# MezzanineConnectors.net
KiCad netlist of a schematic drawn in Altium Designer
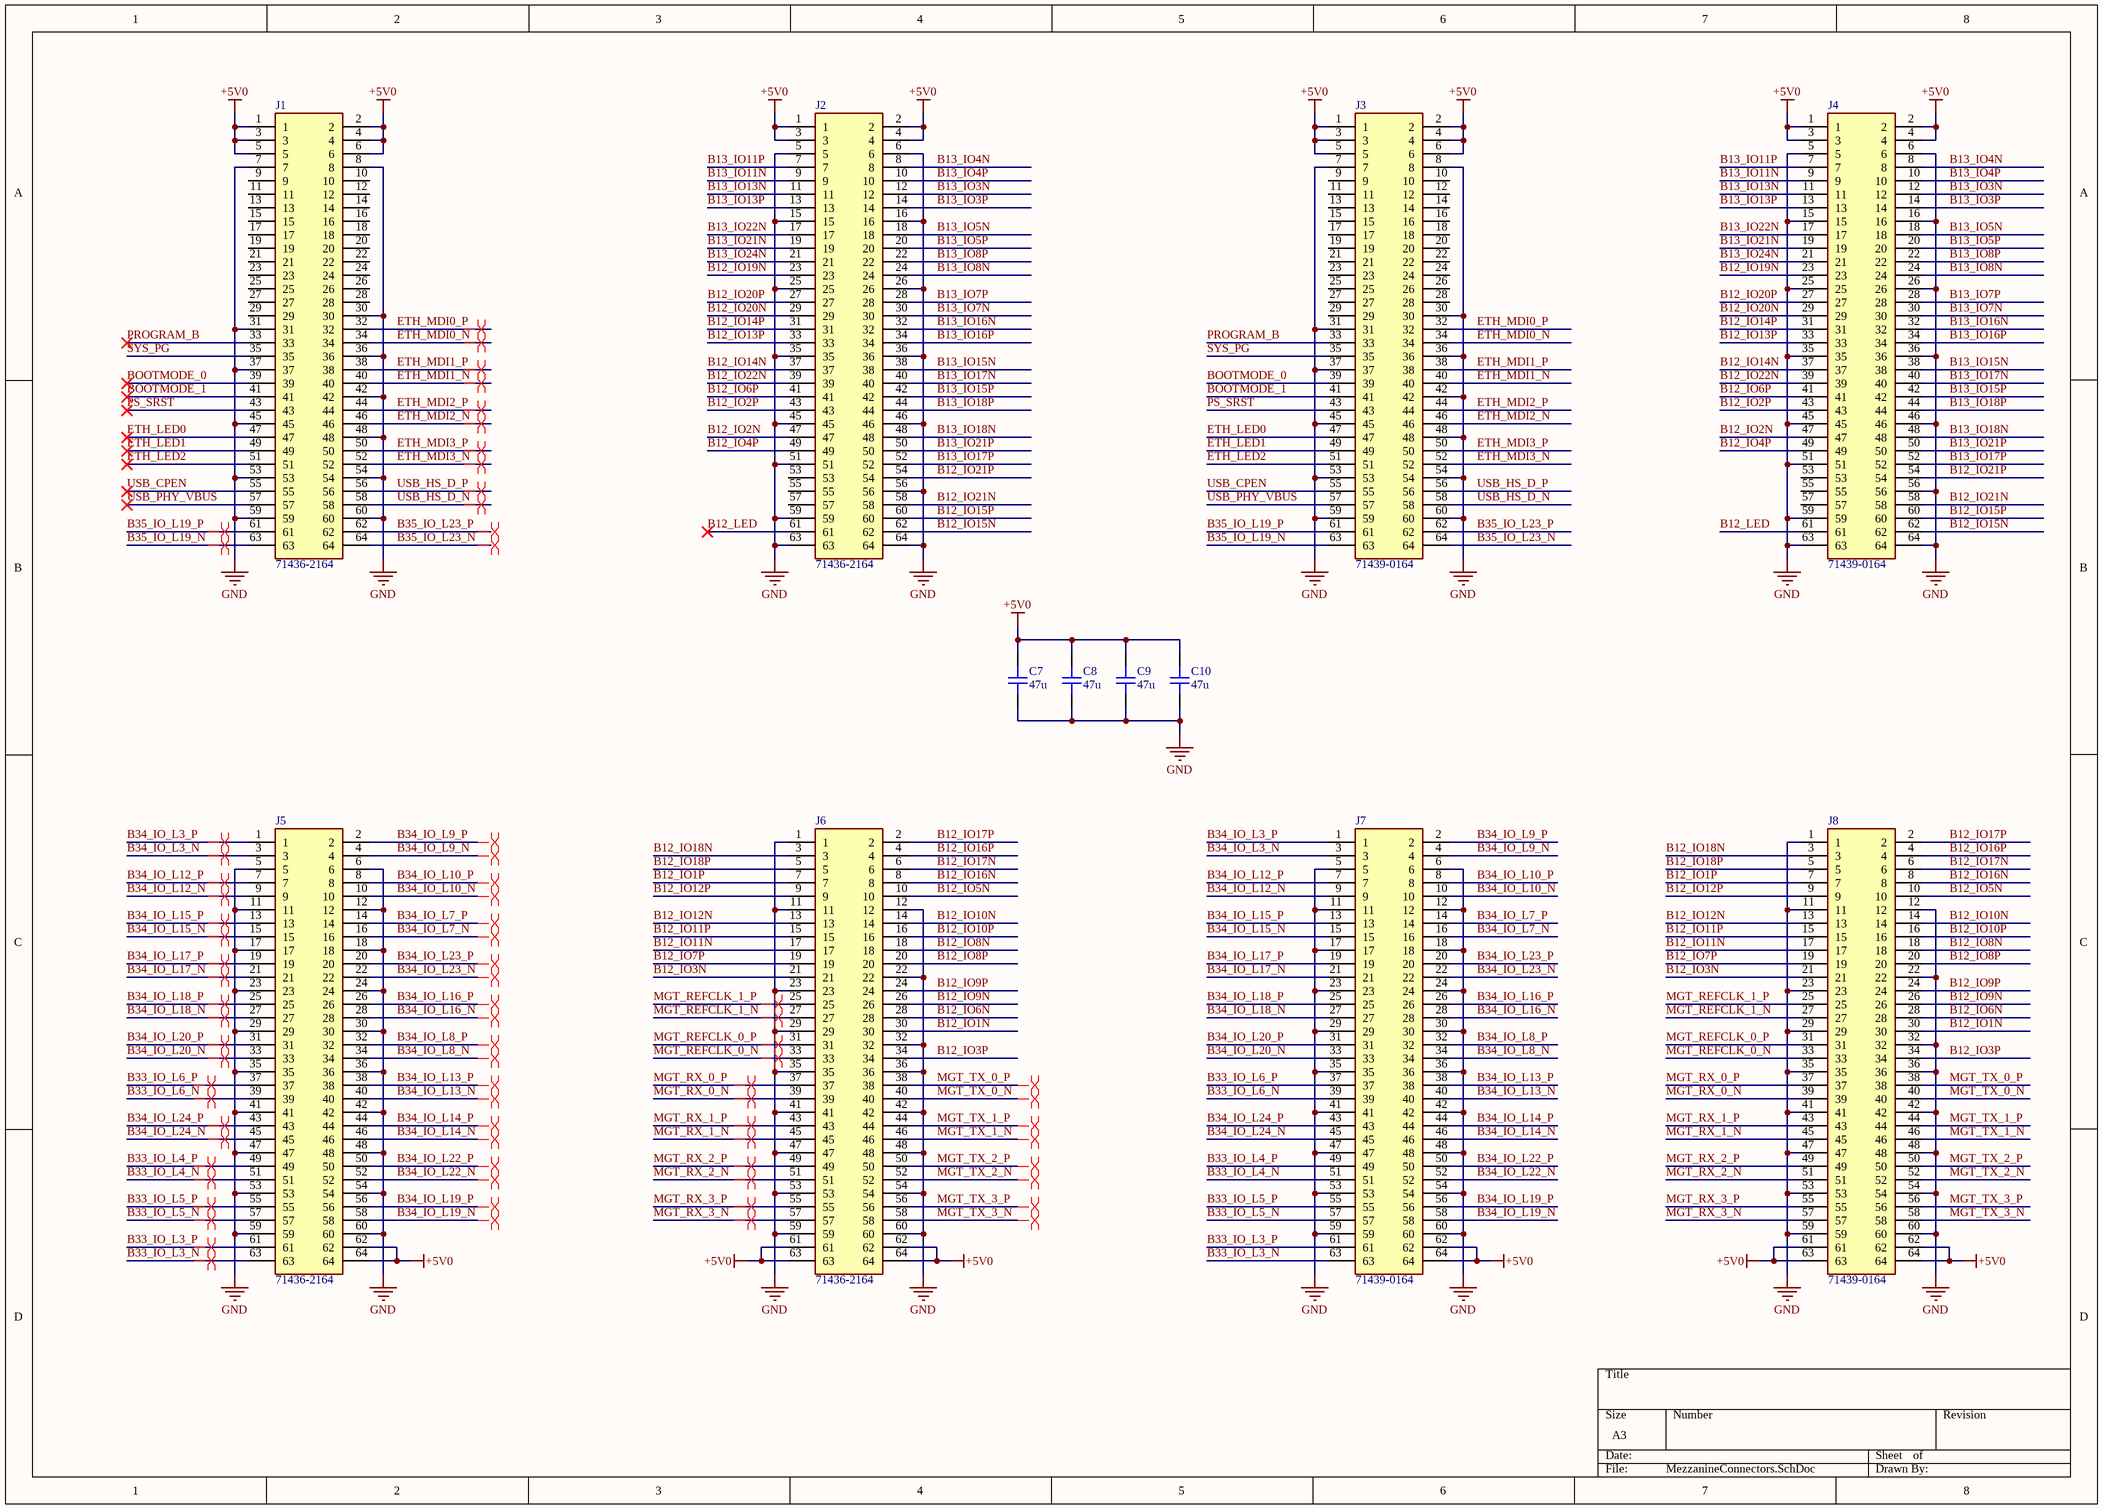
[diagram p0: MezzanineConnectors.SchDoc]

(export (version "E")
  (design (tool "Eeschema 10.0.6"))
  (components
    (comp (ref "C7")
      (value "47u")
      (footprint "CAP_0805")
      (description "Capacitor SMD 0805")
      (libsource (lib "Schematic-Lib-PhilsLab") (part "CAP_0805"))
    )
    (comp (ref "C8")
      (value "47u")
      (footprint "CAP_0805")
      (description "Capacitor SMD 0805")
      (libsource (lib "Schematic-Lib-PhilsLab") (part "CAP_0805"))
    )
    (comp (ref "C9")
      (value "47u")
      (footprint "CAP_0805")
      (description "Capacitor SMD 0805")
      (libsource (lib "Schematic-Lib-PhilsLab") (part "CAP_0805"))
    )
    (comp (ref "C10")
      (value "47u")
      (footprint "CAP_0805")
      (description "Capacitor SMD 0805")
      (libsource (lib "Schematic-Lib-PhilsLab") (part "CAP_0805"))
    )
    (comp (ref "J1")
      (value "71436-2164")
      (footprint "714362164")
      (fields (field (name "MOUSER PART NUMBER") "538-71436-2164"))
      (libsource (lib "XC7Z030SCHLib") (part "71436-2164"))
    )
    (comp (ref "J2")
      (value "71436-2164")
      (footprint "714362164")
      (fields (field (name "MOUSER PART NUMBER") "538-71436-2164"))
      (libsource (lib "XC7Z030SCHLib") (part "71436-2164"))
    )
    (comp (ref "J3")
      (value "71439-0164")
      (footprint "XC7Z030PCBLib:714390164")
      (description "Board to Board & Mezzanine Connectors PMC RECEPTACLE SMT")
      (fields (field (name "MOUSER PART NUMBER") "538-71439-0164"))
      (libsource (lib "XC7Z030SCHLib") (part "71439-0164"))
    )
    (comp (ref "J4")
      (value "71439-0164")
      (footprint "XC7Z030PCBLib:714390164")
      (description "Board to Board & Mezzanine Connectors PMC RECEPTACLE SMT")
      (fields (field (name "MOUSER PART NUMBER") "538-71439-0164"))
      (libsource (lib "XC7Z030SCHLib") (part "71439-0164"))
    )
    (comp (ref "J5")
      (value "71436-2164")
      (footprint "714362164")
      (fields (field (name "MOUSER PART NUMBER") "538-71436-2164"))
      (libsource (lib "XC7Z030SCHLib") (part "71436-2164"))
    )
    (comp (ref "J6")
      (value "71436-2164")
      (footprint "714362164")
      (fields (field (name "MOUSER PART NUMBER") "538-71436-2164"))
      (libsource (lib "XC7Z030SCHLib") (part "71436-2164"))
    )
    (comp (ref "J7")
      (value "71439-0164")
      (footprint "XC7Z030PCBLib:714390164")
      (description "Board to Board & Mezzanine Connectors PMC RECEPTACLE SMT")
      (fields (field (name "MOUSER PART NUMBER") "538-71439-0164"))
      (libsource (lib "XC7Z030SCHLib") (part "71439-0164"))
    )
    (comp (ref "J8")
      (value "71439-0164")
      (footprint "XC7Z030PCBLib:714390164")
      (description "Board to Board & Mezzanine Connectors PMC RECEPTACLE SMT")
      (fields (field (name "MOUSER PART NUMBER") "538-71439-0164"))
      (libsource (lib "XC7Z030SCHLib") (part "71439-0164"))
    )
  )
  (nets
    (net (code "1") (name "+5V0") (class "Default")
      (node (ref "C10") (pin "2") (pinfunction "2_2") (pintype "passive"))
      (node (ref "C7") (pin "2") (pinfunction "2_2") (pintype "passive"))
      (node (ref "C8") (pin "2") (pinfunction "2_2") (pintype "passive"))
      (node (ref "C9") (pin "2") (pinfunction "2_2") (pintype "passive"))
      (node (ref "J1") (pin "1") (pinfunction "1_1") (pintype "passive"))
      (node (ref "J1") (pin "2") (pinfunction "2_2") (pintype "passive"))
      (node (ref "J1") (pin "3") (pinfunction "3_3") (pintype "passive"))
      (node (ref "J1") (pin "4") (pinfunction "4_4") (pintype "passive"))
      (node (ref "J1") (pin "5") (pinfunction "5_5") (pintype "passive"))
      (node (ref "J1") (pin "6") (pinfunction "6_6") (pintype "passive"))
      (node (ref "J2") (pin "1") (pinfunction "1_1") (pintype "passive"))
      (node (ref "J2") (pin "2") (pinfunction "2_2") (pintype "passive"))
      (node (ref "J2") (pin "3") (pinfunction "3_3") (pintype "passive"))
      (node (ref "J2") (pin "4") (pinfunction "4_4") (pintype "passive"))
      (node (ref "J3") (pin "1") (pinfunction "1_1") (pintype "passive"))
      (node (ref "J3") (pin "2") (pinfunction "2_2") (pintype "passive"))
      (node (ref "J3") (pin "3") (pinfunction "3_3") (pintype "passive"))
      (node (ref "J3") (pin "4") (pinfunction "4_4") (pintype "passive"))
      (node (ref "J3") (pin "5") (pinfunction "5_5") (pintype "passive"))
      (node (ref "J3") (pin "6") (pinfunction "6_6") (pintype "passive"))
      (node (ref "J4") (pin "1") (pinfunction "1_1") (pintype "passive"))
      (node (ref "J4") (pin "2") (pinfunction "2_2") (pintype "passive"))
      (node (ref "J4") (pin "3") (pinfunction "3_3") (pintype "passive"))
      (node (ref "J4") (pin "4") (pinfunction "4_4") (pintype "passive"))
      (node (ref "J5") (pin "62") (pinfunction "62_62") (pintype "passive"))
      (node (ref "J5") (pin "64") (pinfunction "64_64") (pintype "passive"))
      (node (ref "J6") (pin "61") (pinfunction "61_61") (pintype "passive"))
      (node (ref "J6") (pin "62") (pinfunction "62_62") (pintype "passive"))
      (node (ref "J6") (pin "63") (pinfunction "63_63") (pintype "passive"))
      (node (ref "J6") (pin "64") (pinfunction "64_64") (pintype "passive"))
      (node (ref "J7") (pin "62") (pinfunction "62_62") (pintype "passive"))
      (node (ref "J7") (pin "64") (pinfunction "64_64") (pintype "passive"))
      (node (ref "J8") (pin "61") (pinfunction "61_61") (pintype "passive"))
      (node (ref "J8") (pin "62") (pinfunction "62_62") (pintype "passive"))
      (node (ref "J8") (pin "63") (pinfunction "63_63") (pintype "passive"))
      (node (ref "J8") (pin "64") (pinfunction "64_64") (pintype "passive"))
    )
    (net (code "2") (name "/B12_IO1N") (class "Default")
      (node (ref "J6") (pin "30") (pinfunction "30_30") (pintype "passive"))
      (node (ref "J8") (pin "30") (pinfunction "30_30") (pintype "passive"))
    )
    (net (code "3") (name "/B12_IO1P") (class "Default")
      (node (ref "J6") (pin "7") (pinfunction "7_7") (pintype "passive"))
      (node (ref "J8") (pin "7") (pinfunction "7_7") (pintype "passive"))
    )
    (net (code "4") (name "/B12_IO2N") (class "Default")
      (node (ref "J2") (pin "47") (pinfunction "47_47") (pintype "passive"))
      (node (ref "J4") (pin "47") (pinfunction "47_47") (pintype "passive"))
    )
    (net (code "5") (name "/B12_IO2P") (class "Default")
      (node (ref "J2") (pin "43") (pinfunction "43_43") (pintype "passive"))
      (node (ref "J4") (pin "43") (pinfunction "43_43") (pintype "passive"))
    )
    (net (code "6") (name "/B12_IO3N") (class "Default")
      (node (ref "J6") (pin "21") (pinfunction "21_21") (pintype "passive"))
      (node (ref "J8") (pin "21") (pinfunction "21_21") (pintype "passive"))
    )
    (net (code "7") (name "/B12_IO3P") (class "Default")
      (node (ref "J6") (pin "34") (pinfunction "34_34") (pintype "passive"))
      (node (ref "J8") (pin "34") (pinfunction "34_34") (pintype "passive"))
    )
    (net (code "8") (name "/B12_IO4P") (class "Default")
      (node (ref "J2") (pin "49") (pinfunction "49_49") (pintype "passive"))
      (node (ref "J4") (pin "49") (pinfunction "49_49") (pintype "passive"))
    )
    (net (code "9") (name "/B12_IO5N") (class "Default")
      (node (ref "J6") (pin "10") (pinfunction "10_10") (pintype "passive"))
      (node (ref "J8") (pin "10") (pinfunction "10_10") (pintype "passive"))
    )
    (net (code "10") (name "/B12_IO6N") (class "Default")
      (node (ref "J6") (pin "28") (pinfunction "28_28") (pintype "passive"))
      (node (ref "J8") (pin "28") (pinfunction "28_28") (pintype "passive"))
    )
    (net (code "11") (name "/B12_IO6P") (class "Default")
      (node (ref "J2") (pin "41") (pinfunction "41_41") (pintype "passive"))
      (node (ref "J4") (pin "41") (pinfunction "41_41") (pintype "passive"))
    )
    (net (code "12") (name "/B12_IO7P") (class "Default")
      (node (ref "J6") (pin "19") (pinfunction "19_19") (pintype "passive"))
      (node (ref "J8") (pin "19") (pinfunction "19_19") (pintype "passive"))
    )
    (net (code "13") (name "/B12_IO8N") (class "Default")
      (node (ref "J6") (pin "18") (pinfunction "18_18") (pintype "passive"))
      (node (ref "J8") (pin "18") (pinfunction "18_18") (pintype "passive"))
    )
    (net (code "14") (name "/B12_IO8P") (class "Default")
      (node (ref "J6") (pin "20") (pinfunction "20_20") (pintype "passive"))
      (node (ref "J8") (pin "20") (pinfunction "20_20") (pintype "passive"))
    )
    (net (code "15") (name "/B12_IO9N") (class "Default")
      (node (ref "J6") (pin "26") (pinfunction "26_26") (pintype "passive"))
      (node (ref "J8") (pin "26") (pinfunction "26_26") (pintype "passive"))
    )
    (net (code "16") (name "/B12_IO9P") (class "Default")
      (node (ref "J6") (pin "24") (pinfunction "24_24") (pintype "passive"))
      (node (ref "J8") (pin "24") (pinfunction "24_24") (pintype "passive"))
    )
    (net (code "17") (name "/B12_IO10N") (class "Default")
      (node (ref "J6") (pin "14") (pinfunction "14_14") (pintype "passive"))
      (node (ref "J8") (pin "14") (pinfunction "14_14") (pintype "passive"))
    )
    (net (code "18") (name "/B12_IO10P") (class "Default")
      (node (ref "J6") (pin "16") (pinfunction "16_16") (pintype "passive"))
      (node (ref "J8") (pin "16") (pinfunction "16_16") (pintype "passive"))
    )
    (net (code "19") (name "/B12_IO11N") (class "Default")
      (node (ref "J6") (pin "17") (pinfunction "17_17") (pintype "passive"))
      (node (ref "J8") (pin "17") (pinfunction "17_17") (pintype "passive"))
    )
    (net (code "20") (name "/B12_IO11P") (class "Default")
      (node (ref "J6") (pin "15") (pinfunction "15_15") (pintype "passive"))
      (node (ref "J8") (pin "15") (pinfunction "15_15") (pintype "passive"))
    )
    (net (code "21") (name "/B12_IO12N") (class "Default")
      (node (ref "J6") (pin "13") (pinfunction "13_13") (pintype "passive"))
      (node (ref "J8") (pin "13") (pinfunction "13_13") (pintype "passive"))
    )
    (net (code "22") (name "/B12_IO12P") (class "Default")
      (node (ref "J6") (pin "9") (pinfunction "9_9") (pintype "passive"))
      (node (ref "J8") (pin "9") (pinfunction "9_9") (pintype "passive"))
    )
    (net (code "23") (name "/B12_IO13P") (class "Default")
      (node (ref "J2") (pin "33") (pinfunction "33_33") (pintype "passive"))
      (node (ref "J4") (pin "33") (pinfunction "33_33") (pintype "passive"))
    )
    (net (code "24") (name "/B12_IO14N") (class "Default")
      (node (ref "J2") (pin "37") (pinfunction "37_37") (pintype "passive"))
      (node (ref "J4") (pin "37") (pinfunction "37_37") (pintype "passive"))
    )
    (net (code "25") (name "/B12_IO14P") (class "Default")
      (node (ref "J2") (pin "31") (pinfunction "31_31") (pintype "passive"))
      (node (ref "J4") (pin "31") (pinfunction "31_31") (pintype "passive"))
    )
    (net (code "26") (name "/B12_IO15N") (class "Default")
      (node (ref "J2") (pin "62") (pinfunction "62_62") (pintype "passive"))
      (node (ref "J4") (pin "62") (pinfunction "62_62") (pintype "passive"))
    )
    (net (code "27") (name "/B12_IO15P") (class "Default")
      (node (ref "J2") (pin "60") (pinfunction "60_60") (pintype "passive"))
      (node (ref "J4") (pin "60") (pinfunction "60_60") (pintype "passive"))
    )
    (net (code "28") (name "/B12_IO16N") (class "Default")
      (node (ref "J6") (pin "8") (pinfunction "8_8") (pintype "passive"))
      (node (ref "J8") (pin "8") (pinfunction "8_8") (pintype "passive"))
    )
    (net (code "29") (name "/B12_IO16P") (class "Default")
      (node (ref "J6") (pin "4") (pinfunction "4_4") (pintype "passive"))
      (node (ref "J8") (pin "4") (pinfunction "4_4") (pintype "passive"))
    )
    (net (code "30") (name "/B12_IO17N") (class "Default")
      (node (ref "J6") (pin "6") (pinfunction "6_6") (pintype "passive"))
      (node (ref "J8") (pin "6") (pinfunction "6_6") (pintype "passive"))
    )
    (net (code "31") (name "/B12_IO17P") (class "Default")
      (node (ref "J6") (pin "2") (pinfunction "2_2") (pintype "passive"))
      (node (ref "J8") (pin "2") (pinfunction "2_2") (pintype "passive"))
    )
    (net (code "32") (name "/B12_IO18N") (class "Default")
      (node (ref "J6") (pin "3") (pinfunction "3_3") (pintype "passive"))
      (node (ref "J8") (pin "3") (pinfunction "3_3") (pintype "passive"))
    )
    (net (code "33") (name "/B12_IO18P") (class "Default")
      (node (ref "J6") (pin "5") (pinfunction "5_5") (pintype "passive"))
      (node (ref "J8") (pin "5") (pinfunction "5_5") (pintype "passive"))
    )
    (net (code "34") (name "/B12_IO19N") (class "Default")
      (node (ref "J2") (pin "23") (pinfunction "23_23") (pintype "passive"))
      (node (ref "J4") (pin "23") (pinfunction "23_23") (pintype "passive"))
    )
    (net (code "35") (name "/B12_IO20N") (class "Default")
      (node (ref "J2") (pin "29") (pinfunction "29_29") (pintype "passive"))
      (node (ref "J4") (pin "29") (pinfunction "29_29") (pintype "passive"))
    )
    (net (code "36") (name "/B12_IO20P") (class "Default")
      (node (ref "J2") (pin "27") (pinfunction "27_27") (pintype "passive"))
      (node (ref "J4") (pin "27") (pinfunction "27_27") (pintype "passive"))
    )
    (net (code "37") (name "/B12_IO21N") (class "Default")
      (node (ref "J2") (pin "58") (pinfunction "58_58") (pintype "passive"))
      (node (ref "J4") (pin "58") (pinfunction "58_58") (pintype "passive"))
    )
    (net (code "38") (name "/B12_IO21P") (class "Default")
      (node (ref "J2") (pin "54") (pinfunction "54_54") (pintype "passive"))
      (node (ref "J4") (pin "54") (pinfunction "54_54") (pintype "passive"))
    )
    (net (code "39") (name "/B12_IO22N") (class "Default")
      (node (ref "J2") (pin "39") (pinfunction "39_39") (pintype "passive"))
      (node (ref "J4") (pin "39") (pinfunction "39_39") (pintype "passive"))
    )
    (net (code "40") (name "/B12_LED") (class "Default")
      (node (ref "J2") (pin "61") (pinfunction "61_61") (pintype "passive"))
      (node (ref "J4") (pin "61") (pinfunction "61_61") (pintype "passive"))
    )
    (net (code "41") (name "/B13_IO3N") (class "Default")
      (node (ref "J2") (pin "12") (pinfunction "12_12") (pintype "passive"))
      (node (ref "J4") (pin "12") (pinfunction "12_12") (pintype "passive"))
    )
    (net (code "42") (name "/B13_IO3P") (class "Default")
      (node (ref "J2") (pin "14") (pinfunction "14_14") (pintype "passive"))
      (node (ref "J4") (pin "14") (pinfunction "14_14") (pintype "passive"))
    )
    (net (code "43") (name "/B13_IO4N") (class "Default")
      (node (ref "J2") (pin "8") (pinfunction "8_8") (pintype "passive"))
      (node (ref "J4") (pin "8") (pinfunction "8_8") (pintype "passive"))
    )
    (net (code "44") (name "/B13_IO4P") (class "Default")
      (node (ref "J2") (pin "10") (pinfunction "10_10") (pintype "passive"))
      (node (ref "J4") (pin "10") (pinfunction "10_10") (pintype "passive"))
    )
    (net (code "45") (name "/B13_IO5N") (class "Default")
      (node (ref "J2") (pin "18") (pinfunction "18_18") (pintype "passive"))
      (node (ref "J4") (pin "18") (pinfunction "18_18") (pintype "passive"))
    )
    (net (code "46") (name "/B13_IO5P") (class "Default")
      (node (ref "J2") (pin "20") (pinfunction "20_20") (pintype "passive"))
      (node (ref "J4") (pin "20") (pinfunction "20_20") (pintype "passive"))
    )
    (net (code "47") (name "/B13_IO7N") (class "Default")
      (node (ref "J2") (pin "30") (pinfunction "30_30") (pintype "passive"))
      (node (ref "J4") (pin "30") (pinfunction "30_30") (pintype "passive"))
    )
    (net (code "48") (name "/B13_IO7P") (class "Default")
      (node (ref "J2") (pin "28") (pinfunction "28_28") (pintype "passive"))
      (node (ref "J4") (pin "28") (pinfunction "28_28") (pintype "passive"))
    )
    (net (code "49") (name "/B13_IO8N") (class "Default")
      (node (ref "J2") (pin "24") (pinfunction "24_24") (pintype "passive"))
      (node (ref "J4") (pin "24") (pinfunction "24_24") (pintype "passive"))
    )
    (net (code "50") (name "/B13_IO8P") (class "Default")
      (node (ref "J2") (pin "22") (pinfunction "22_22") (pintype "passive"))
      (node (ref "J4") (pin "22") (pinfunction "22_22") (pintype "passive"))
    )
    (net (code "51") (name "/B13_IO11N") (class "Default")
      (node (ref "J2") (pin "9") (pinfunction "9_9") (pintype "passive"))
      (node (ref "J4") (pin "9") (pinfunction "9_9") (pintype "passive"))
    )
    (net (code "52") (name "/B13_IO11P") (class "Default")
      (node (ref "J2") (pin "7") (pinfunction "7_7") (pintype "passive"))
      (node (ref "J4") (pin "7") (pinfunction "7_7") (pintype "passive"))
    )
    (net (code "53") (name "/B13_IO13N") (class "Default")
      (node (ref "J2") (pin "11") (pinfunction "11_11") (pintype "passive"))
      (node (ref "J4") (pin "11") (pinfunction "11_11") (pintype "passive"))
    )
    (net (code "54") (name "/B13_IO13P") (class "Default")
      (node (ref "J2") (pin "13") (pinfunction "13_13") (pintype "passive"))
      (node (ref "J4") (pin "13") (pinfunction "13_13") (pintype "passive"))
    )
    (net (code "55") (name "/B13_IO15N") (class "Default")
      (node (ref "J2") (pin "38") (pinfunction "38_38") (pintype "passive"))
      (node (ref "J4") (pin "38") (pinfunction "38_38") (pintype "passive"))
    )
    (net (code "56") (name "/B13_IO15P") (class "Default")
      (node (ref "J2") (pin "42") (pinfunction "42_42") (pintype "passive"))
      (node (ref "J4") (pin "42") (pinfunction "42_42") (pintype "passive"))
    )
    (net (code "57") (name "/B13_IO16N") (class "Default")
      (node (ref "J2") (pin "32") (pinfunction "32_32") (pintype "passive"))
      (node (ref "J4") (pin "32") (pinfunction "32_32") (pintype "passive"))
    )
    (net (code "58") (name "/B13_IO16P") (class "Default")
      (node (ref "J2") (pin "34") (pinfunction "34_34") (pintype "passive"))
      (node (ref "J4") (pin "34") (pinfunction "34_34") (pintype "passive"))
    )
    (net (code "59") (name "/B13_IO17N") (class "Default")
      (node (ref "J2") (pin "40") (pinfunction "40_40") (pintype "passive"))
      (node (ref "J4") (pin "40") (pinfunction "40_40") (pintype "passive"))
    )
    (net (code "60") (name "/B13_IO17P") (class "Default")
      (node (ref "J2") (pin "52") (pinfunction "52_52") (pintype "passive"))
      (node (ref "J4") (pin "52") (pinfunction "52_52") (pintype "passive"))
    )
    (net (code "61") (name "/B13_IO18N") (class "Default")
      (node (ref "J2") (pin "48") (pinfunction "48_48") (pintype "passive"))
      (node (ref "J4") (pin "48") (pinfunction "48_48") (pintype "passive"))
    )
    (net (code "62") (name "/B13_IO18P") (class "Default")
      (node (ref "J2") (pin "44") (pinfunction "44_44") (pintype "passive"))
      (node (ref "J4") (pin "44") (pinfunction "44_44") (pintype "passive"))
    )
    (net (code "63") (name "/B13_IO21N") (class "Default")
      (node (ref "J2") (pin "19") (pinfunction "19_19") (pintype "passive"))
      (node (ref "J4") (pin "19") (pinfunction "19_19") (pintype "passive"))
    )
    (net (code "64") (name "/B13_IO21P") (class "Default")
      (node (ref "J2") (pin "50") (pinfunction "50_50") (pintype "passive"))
      (node (ref "J4") (pin "50") (pinfunction "50_50") (pintype "passive"))
    )
    (net (code "65") (name "/B13_IO22N") (class "Default")
      (node (ref "J2") (pin "17") (pinfunction "17_17") (pintype "passive"))
      (node (ref "J4") (pin "17") (pinfunction "17_17") (pintype "passive"))
    )
    (net (code "66") (name "/B13_IO24N") (class "Default")
      (node (ref "J2") (pin "21") (pinfunction "21_21") (pintype "passive"))
      (node (ref "J4") (pin "21") (pinfunction "21_21") (pintype "passive"))
    )
    (net (code "67") (name "/B33_IO_L3_N") (class "Default")
      (node (ref "J5") (pin "63") (pinfunction "63_63") (pintype "passive"))
      (node (ref "J7") (pin "63") (pinfunction "63_63") (pintype "passive"))
    )
    (net (code "68") (name "/B33_IO_L3_P") (class "Default")
      (node (ref "J5") (pin "61") (pinfunction "61_61") (pintype "passive"))
      (node (ref "J7") (pin "61") (pinfunction "61_61") (pintype "passive"))
    )
    (net (code "69") (name "/B33_IO_L4_N") (class "Default")
      (node (ref "J5") (pin "51") (pinfunction "51_51") (pintype "passive"))
      (node (ref "J7") (pin "51") (pinfunction "51_51") (pintype "passive"))
    )
    (net (code "70") (name "/B33_IO_L4_P") (class "Default")
      (node (ref "J5") (pin "49") (pinfunction "49_49") (pintype "passive"))
      (node (ref "J7") (pin "49") (pinfunction "49_49") (pintype "passive"))
    )
    (net (code "71") (name "/B33_IO_L5_N") (class "Default")
      (node (ref "J5") (pin "57") (pinfunction "57_57") (pintype "passive"))
      (node (ref "J7") (pin "57") (pinfunction "57_57") (pintype "passive"))
    )
    (net (code "72") (name "/B33_IO_L5_P") (class "Default")
      (node (ref "J5") (pin "55") (pinfunction "55_55") (pintype "passive"))
      (node (ref "J7") (pin "55") (pinfunction "55_55") (pintype "passive"))
    )
    (net (code "73") (name "/B33_IO_L6_N") (class "Default")
      (node (ref "J5") (pin "39") (pinfunction "39_39") (pintype "passive"))
      (node (ref "J7") (pin "39") (pinfunction "39_39") (pintype "passive"))
    )
    (net (code "74") (name "/B33_IO_L6_P") (class "Default")
      (node (ref "J5") (pin "37") (pinfunction "37_37") (pintype "passive"))
      (node (ref "J7") (pin "37") (pinfunction "37_37") (pintype "passive"))
    )
    (net (code "75") (name "/B34_IO_L3_N") (class "Default")
      (node (ref "J5") (pin "3") (pinfunction "3_3") (pintype "passive"))
      (node (ref "J7") (pin "3") (pinfunction "3_3") (pintype "passive"))
    )
    (net (code "76") (name "/B34_IO_L3_P") (class "Default")
      (node (ref "J5") (pin "1") (pinfunction "1_1") (pintype "passive"))
      (node (ref "J7") (pin "1") (pinfunction "1_1") (pintype "passive"))
    )
    (net (code "77") (name "/B34_IO_L7_N") (class "Default")
      (node (ref "J5") (pin "16") (pinfunction "16_16") (pintype "passive"))
      (node (ref "J7") (pin "16") (pinfunction "16_16") (pintype "passive"))
    )
    (net (code "78") (name "/B34_IO_L7_P") (class "Default")
      (node (ref "J5") (pin "14") (pinfunction "14_14") (pintype "passive"))
      (node (ref "J7") (pin "14") (pinfunction "14_14") (pintype "passive"))
    )
    (net (code "79") (name "/B34_IO_L8_N") (class "Default")
      (node (ref "J5") (pin "34") (pinfunction "34_34") (pintype "passive"))
      (node (ref "J7") (pin "34") (pinfunction "34_34") (pintype "passive"))
    )
    (net (code "80") (name "/B34_IO_L8_P") (class "Default")
      (node (ref "J5") (pin "32") (pinfunction "32_32") (pintype "passive"))
      (node (ref "J7") (pin "32") (pinfunction "32_32") (pintype "passive"))
    )
    (net (code "81") (name "/B34_IO_L9_N") (class "Default")
      (node (ref "J5") (pin "4") (pinfunction "4_4") (pintype "passive"))
      (node (ref "J7") (pin "4") (pinfunction "4_4") (pintype "passive"))
    )
    (net (code "82") (name "/B34_IO_L9_P") (class "Default")
      (node (ref "J5") (pin "2") (pinfunction "2_2") (pintype "passive"))
      (node (ref "J7") (pin "2") (pinfunction "2_2") (pintype "passive"))
    )
    (net (code "83") (name "/B34_IO_L10_N") (class "Default")
      (node (ref "J5") (pin "10") (pinfunction "10_10") (pintype "passive"))
      (node (ref "J7") (pin "10") (pinfunction "10_10") (pintype "passive"))
    )
    (net (code "84") (name "/B34_IO_L10_P") (class "Default")
      (node (ref "J5") (pin "8") (pinfunction "8_8") (pintype "passive"))
      (node (ref "J7") (pin "8") (pinfunction "8_8") (pintype "passive"))
    )
    (net (code "85") (name "/B34_IO_L12_N") (class "Default")
      (node (ref "J5") (pin "9") (pinfunction "9_9") (pintype "passive"))
      (node (ref "J7") (pin "9") (pinfunction "9_9") (pintype "passive"))
    )
    (net (code "86") (name "/B34_IO_L12_P") (class "Default")
      (node (ref "J5") (pin "7") (pinfunction "7_7") (pintype "passive"))
      (node (ref "J7") (pin "7") (pinfunction "7_7") (pintype "passive"))
    )
    (net (code "87") (name "/B34_IO_L13_N") (class "Default")
      (node (ref "J5") (pin "40") (pinfunction "40_40") (pintype "passive"))
      (node (ref "J7") (pin "40") (pinfunction "40_40") (pintype "passive"))
    )
    (net (code "88") (name "/B34_IO_L13_P") (class "Default")
      (node (ref "J5") (pin "38") (pinfunction "38_38") (pintype "passive"))
      (node (ref "J7") (pin "38") (pinfunction "38_38") (pintype "passive"))
    )
    (net (code "89") (name "/B34_IO_L14_N") (class "Default")
      (node (ref "J5") (pin "46") (pinfunction "46_46") (pintype "passive"))
      (node (ref "J7") (pin "46") (pinfunction "46_46") (pintype "passive"))
    )
    (net (code "90") (name "/B34_IO_L14_P") (class "Default")
      (node (ref "J5") (pin "44") (pinfunction "44_44") (pintype "passive"))
      (node (ref "J7") (pin "44") (pinfunction "44_44") (pintype "passive"))
    )
    (net (code "91") (name "/B34_IO_L15_N") (class "Default")
      (node (ref "J5") (pin "15") (pinfunction "15_15") (pintype "passive"))
      (node (ref "J7") (pin "15") (pinfunction "15_15") (pintype "passive"))
    )
    (net (code "92") (name "/B34_IO_L15_P") (class "Default")
      (node (ref "J5") (pin "13") (pinfunction "13_13") (pintype "passive"))
      (node (ref "J7") (pin "13") (pinfunction "13_13") (pintype "passive"))
    )
    (net (code "93") (name "/B34_IO_L16_N") (class "Default")
      (node (ref "J5") (pin "28") (pinfunction "28_28") (pintype "passive"))
      (node (ref "J7") (pin "28") (pinfunction "28_28") (pintype "passive"))
    )
    (net (code "94") (name "/B34_IO_L16_P") (class "Default")
      (node (ref "J5") (pin "26") (pinfunction "26_26") (pintype "passive"))
      (node (ref "J7") (pin "26") (pinfunction "26_26") (pintype "passive"))
    )
    (net (code "95") (name "/B34_IO_L17_N") (class "Default")
      (node (ref "J5") (pin "21") (pinfunction "21_21") (pintype "passive"))
      (node (ref "J7") (pin "21") (pinfunction "21_21") (pintype "passive"))
    )
    (net (code "96") (name "/B34_IO_L17_P") (class "Default")
      (node (ref "J5") (pin "19") (pinfunction "19_19") (pintype "passive"))
      (node (ref "J7") (pin "19") (pinfunction "19_19") (pintype "passive"))
    )
    (net (code "97") (name "/B34_IO_L18_N") (class "Default")
      (node (ref "J5") (pin "27") (pinfunction "27_27") (pintype "passive"))
      (node (ref "J7") (pin "27") (pinfunction "27_27") (pintype "passive"))
    )
    (net (code "98") (name "/B34_IO_L18_P") (class "Default")
      (node (ref "J5") (pin "25") (pinfunction "25_25") (pintype "passive"))
      (node (ref "J7") (pin "25") (pinfunction "25_25") (pintype "passive"))
    )
    (net (code "99") (name "/B34_IO_L19_N") (class "Default")
      (node (ref "J5") (pin "58") (pinfunction "58_58") (pintype "passive"))
      (node (ref "J7") (pin "58") (pinfunction "58_58") (pintype "passive"))
    )
    (net (code "100") (name "/B34_IO_L19_P") (class "Default")
      (node (ref "J5") (pin "56") (pinfunction "56_56") (pintype "passive"))
      (node (ref "J7") (pin "56") (pinfunction "56_56") (pintype "passive"))
    )
    (net (code "101") (name "/B34_IO_L20_N") (class "Default")
      (node (ref "J5") (pin "33") (pinfunction "33_33") (pintype "passive"))
      (node (ref "J7") (pin "33") (pinfunction "33_33") (pintype "passive"))
    )
    (net (code "102") (name "/B34_IO_L20_P") (class "Default")
      (node (ref "J5") (pin "31") (pinfunction "31_31") (pintype "passive"))
      (node (ref "J7") (pin "31") (pinfunction "31_31") (pintype "passive"))
    )
    (net (code "103") (name "/B34_IO_L22_N") (class "Default")
      (node (ref "J5") (pin "52") (pinfunction "52_52") (pintype "passive"))
      (node (ref "J7") (pin "52") (pinfunction "52_52") (pintype "passive"))
    )
    (net (code "104") (name "/B34_IO_L22_P") (class "Default")
      (node (ref "J5") (pin "50") (pinfunction "50_50") (pintype "passive"))
      (node (ref "J7") (pin "50") (pinfunction "50_50") (pintype "passive"))
    )
    (net (code "105") (name "/B34_IO_L23_N") (class "Default")
      (node (ref "J5") (pin "22") (pinfunction "22_22") (pintype "passive"))
      (node (ref "J7") (pin "22") (pinfunction "22_22") (pintype "passive"))
    )
    (net (code "106") (name "/B34_IO_L23_P") (class "Default")
      (node (ref "J5") (pin "20") (pinfunction "20_20") (pintype "passive"))
      (node (ref "J7") (pin "20") (pinfunction "20_20") (pintype "passive"))
    )
    (net (code "107") (name "/B34_IO_L24_N") (class "Default")
      (node (ref "J5") (pin "45") (pinfunction "45_45") (pintype "passive"))
      (node (ref "J7") (pin "45") (pinfunction "45_45") (pintype "passive"))
    )
    (net (code "108") (name "/B34_IO_L24_P") (class "Default")
      (node (ref "J5") (pin "43") (pinfunction "43_43") (pintype "passive"))
      (node (ref "J7") (pin "43") (pinfunction "43_43") (pintype "passive"))
    )
    (net (code "109") (name "/B35_IO_L19_N") (class "Default")
      (node (ref "J1") (pin "63") (pinfunction "63_63") (pintype "passive"))
      (node (ref "J3") (pin "63") (pinfunction "63_63") (pintype "passive"))
    )
    (net (code "110") (name "/B35_IO_L19_P") (class "Default")
      (node (ref "J1") (pin "61") (pinfunction "61_61") (pintype "passive"))
      (node (ref "J3") (pin "61") (pinfunction "61_61") (pintype "passive"))
    )
    (net (code "111") (name "/B35_IO_L23_N") (class "Default")
      (node (ref "J1") (pin "64") (pinfunction "64_64") (pintype "passive"))
      (node (ref "J3") (pin "64") (pinfunction "64_64") (pintype "passive"))
    )
    (net (code "112") (name "/B35_IO_L23_P") (class "Default")
      (node (ref "J1") (pin "62") (pinfunction "62_62") (pintype "passive"))
      (node (ref "J3") (pin "62") (pinfunction "62_62") (pintype "passive"))
    )
    (net (code "113") (name "/BOOTMODE_0") (class "Default")
      (node (ref "J1") (pin "39") (pinfunction "39_39") (pintype "passive"))
      (node (ref "J3") (pin "39") (pinfunction "39_39") (pintype "passive"))
    )
    (net (code "114") (name "/BOOTMODE_1") (class "Default")
      (node (ref "J1") (pin "41") (pinfunction "41_41") (pintype "passive"))
      (node (ref "J3") (pin "41") (pinfunction "41_41") (pintype "passive"))
    )
    (net (code "115") (name "/ETH_LED0") (class "Default")
      (node (ref "J1") (pin "47") (pinfunction "47_47") (pintype "passive"))
      (node (ref "J3") (pin "47") (pinfunction "47_47") (pintype "passive"))
    )
    (net (code "116") (name "/ETH_LED1") (class "Default")
      (node (ref "J1") (pin "49") (pinfunction "49_49") (pintype "passive"))
      (node (ref "J3") (pin "49") (pinfunction "49_49") (pintype "passive"))
    )
    (net (code "117") (name "/ETH_LED2") (class "Default")
      (node (ref "J1") (pin "51") (pinfunction "51_51") (pintype "passive"))
      (node (ref "J3") (pin "51") (pinfunction "51_51") (pintype "passive"))
    )
    (net (code "118") (name "/ETH_MDI0_N") (class "Default")
      (node (ref "J1") (pin "34") (pinfunction "34_34") (pintype "passive"))
      (node (ref "J3") (pin "34") (pinfunction "34_34") (pintype "passive"))
    )
    (net (code "119") (name "/ETH_MDI0_P") (class "Default")
      (node (ref "J1") (pin "32") (pinfunction "32_32") (pintype "passive"))
      (node (ref "J3") (pin "32") (pinfunction "32_32") (pintype "passive"))
    )
    (net (code "120") (name "/ETH_MDI1_N") (class "Default")
      (node (ref "J1") (pin "40") (pinfunction "40_40") (pintype "passive"))
      (node (ref "J3") (pin "40") (pinfunction "40_40") (pintype "passive"))
    )
    (net (code "121") (name "/ETH_MDI1_P") (class "Default")
      (node (ref "J1") (pin "38") (pinfunction "38_38") (pintype "passive"))
      (node (ref "J3") (pin "38") (pinfunction "38_38") (pintype "passive"))
    )
    (net (code "122") (name "/ETH_MDI2_N") (class "Default")
      (node (ref "J1") (pin "46") (pinfunction "46_46") (pintype "passive"))
      (node (ref "J3") (pin "46") (pinfunction "46_46") (pintype "passive"))
    )
    (net (code "123") (name "/ETH_MDI2_P") (class "Default")
      (node (ref "J1") (pin "44") (pinfunction "44_44") (pintype "passive"))
      (node (ref "J3") (pin "44") (pinfunction "44_44") (pintype "passive"))
    )
    (net (code "124") (name "/ETH_MDI3_N") (class "Default")
      (node (ref "J1") (pin "52") (pinfunction "52_52") (pintype "passive"))
      (node (ref "J3") (pin "52") (pinfunction "52_52") (pintype "passive"))
    )
    (net (code "125") (name "/ETH_MDI3_P") (class "Default")
      (node (ref "J1") (pin "50") (pinfunction "50_50") (pintype "passive"))
      (node (ref "J3") (pin "50") (pinfunction "50_50") (pintype "passive"))
    )
    (net (code "126") (name "/MGT_REFCLK_0_N") (class "Default")
      (node (ref "J6") (pin "33") (pinfunction "33_33") (pintype "passive"))
      (node (ref "J8") (pin "33") (pinfunction "33_33") (pintype "passive"))
    )
    (net (code "127") (name "/MGT_REFCLK_0_P") (class "Default")
      (node (ref "J6") (pin "31") (pinfunction "31_31") (pintype "passive"))
      (node (ref "J8") (pin "31") (pinfunction "31_31") (pintype "passive"))
    )
    (net (code "128") (name "/MGT_REFCLK_1_N") (class "Default")
      (node (ref "J6") (pin "27") (pinfunction "27_27") (pintype "passive"))
      (node (ref "J8") (pin "27") (pinfunction "27_27") (pintype "passive"))
    )
    (net (code "129") (name "/MGT_REFCLK_1_P") (class "Default")
      (node (ref "J6") (pin "25") (pinfunction "25_25") (pintype "passive"))
      (node (ref "J8") (pin "25") (pinfunction "25_25") (pintype "passive"))
    )
    (net (code "130") (name "/MGT_RX_0_N") (class "Default")
      (node (ref "J6") (pin "39") (pinfunction "39_39") (pintype "passive"))
      (node (ref "J8") (pin "39") (pinfunction "39_39") (pintype "passive"))
    )
    (net (code "131") (name "/MGT_RX_0_P") (class "Default")
      (node (ref "J6") (pin "37") (pinfunction "37_37") (pintype "passive"))
      (node (ref "J8") (pin "37") (pinfunction "37_37") (pintype "passive"))
    )
    (net (code "132") (name "/MGT_RX_1_N") (class "Default")
      (node (ref "J6") (pin "45") (pinfunction "45_45") (pintype "passive"))
      (node (ref "J8") (pin "45") (pinfunction "45_45") (pintype "passive"))
    )
    (net (code "133") (name "/MGT_RX_1_P") (class "Default")
      (node (ref "J6") (pin "43") (pinfunction "43_43") (pintype "passive"))
      (node (ref "J8") (pin "43") (pinfunction "43_43") (pintype "passive"))
    )
    (net (code "134") (name "/MGT_RX_2_N") (class "Default")
      (node (ref "J6") (pin "51") (pinfunction "51_51") (pintype "passive"))
      (node (ref "J8") (pin "51") (pinfunction "51_51") (pintype "passive"))
    )
    (net (code "135") (name "/MGT_RX_2_P") (class "Default")
      (node (ref "J6") (pin "49") (pinfunction "49_49") (pintype "passive"))
      (node (ref "J8") (pin "49") (pinfunction "49_49") (pintype "passive"))
    )
    (net (code "136") (name "/MGT_RX_3_N") (class "Default")
      (node (ref "J6") (pin "57") (pinfunction "57_57") (pintype "passive"))
      (node (ref "J8") (pin "57") (pinfunction "57_57") (pintype "passive"))
    )
    (net (code "137") (name "/MGT_RX_3_P") (class "Default")
      (node (ref "J6") (pin "55") (pinfunction "55_55") (pintype "passive"))
      (node (ref "J8") (pin "55") (pinfunction "55_55") (pintype "passive"))
    )
    (net (code "138") (name "/MGT_TX_0_N") (class "Default")
      (node (ref "J6") (pin "40") (pinfunction "40_40") (pintype "passive"))
      (node (ref "J8") (pin "40") (pinfunction "40_40") (pintype "passive"))
    )
    (net (code "139") (name "/MGT_TX_0_P") (class "Default")
      (node (ref "J6") (pin "38") (pinfunction "38_38") (pintype "passive"))
      (node (ref "J8") (pin "38") (pinfunction "38_38") (pintype "passive"))
    )
    (net (code "140") (name "/MGT_TX_1_N") (class "Default")
      (node (ref "J6") (pin "46") (pinfunction "46_46") (pintype "passive"))
      (node (ref "J8") (pin "46") (pinfunction "46_46") (pintype "passive"))
    )
    (net (code "141") (name "/MGT_TX_1_P") (class "Default")
      (node (ref "J6") (pin "44") (pinfunction "44_44") (pintype "passive"))
      (node (ref "J8") (pin "44") (pinfunction "44_44") (pintype "passive"))
    )
    (net (code "142") (name "/MGT_TX_2_N") (class "Default")
      (node (ref "J6") (pin "52") (pinfunction "52_52") (pintype "passive"))
      (node (ref "J8") (pin "52") (pinfunction "52_52") (pintype "passive"))
    )
    (net (code "143") (name "/MGT_TX_2_P") (class "Default")
      (node (ref "J6") (pin "50") (pinfunction "50_50") (pintype "passive"))
      (node (ref "J8") (pin "50") (pinfunction "50_50") (pintype "passive"))
    )
    (net (code "144") (name "/MGT_TX_3_N") (class "Default")
      (node (ref "J6") (pin "58") (pinfunction "58_58") (pintype "passive"))
      (node (ref "J8") (pin "58") (pinfunction "58_58") (pintype "passive"))
    )
    (net (code "145") (name "/MGT_TX_3_P") (class "Default")
      (node (ref "J6") (pin "56") (pinfunction "56_56") (pintype "passive"))
      (node (ref "J8") (pin "56") (pinfunction "56_56") (pintype "passive"))
    )
    (net (code "146") (name "/PROGRAM_B") (class "Default")
      (node (ref "J1") (pin "33") (pinfunction "33_33") (pintype "passive"))
      (node (ref "J3") (pin "33") (pinfunction "33_33") (pintype "passive"))
    )
    (net (code "147") (name "/PS_SRST") (class "Default")
      (node (ref "J1") (pin "43") (pinfunction "43_43") (pintype "passive"))
      (node (ref "J3") (pin "43") (pinfunction "43_43") (pintype "passive"))
    )
    (net (code "148") (name "/SYS_PG") (class "Default")
      (node (ref "J1") (pin "35") (pinfunction "35_35") (pintype "passive"))
      (node (ref "J3") (pin "35") (pinfunction "35_35") (pintype "passive"))
    )
    (net (code "149") (name "/USB_CPEN") (class "Default")
      (node (ref "J1") (pin "55") (pinfunction "55_55") (pintype "passive"))
      (node (ref "J3") (pin "55") (pinfunction "55_55") (pintype "passive"))
    )
    (net (code "150") (name "/USB_HS_D_N") (class "Default")
      (node (ref "J1") (pin "58") (pinfunction "58_58") (pintype "passive"))
      (node (ref "J3") (pin "58") (pinfunction "58_58") (pintype "passive"))
    )
    (net (code "151") (name "/USB_HS_D_P") (class "Default")
      (node (ref "J1") (pin "56") (pinfunction "56_56") (pintype "passive"))
      (node (ref "J3") (pin "56") (pinfunction "56_56") (pintype "passive"))
    )
    (net (code "152") (name "/USB_PHY_VBUS") (class "Default")
      (node (ref "J1") (pin "57") (pinfunction "57_57") (pintype "passive"))
      (node (ref "J3") (pin "57") (pinfunction "57_57") (pintype "passive"))
    )
    (net (code "153") (name "GND") (class "Default")
      (node (ref "C10") (pin "1") (pinfunction "1_1") (pintype "passive"))
      (node (ref "C7") (pin "1") (pinfunction "1_1") (pintype "passive"))
      (node (ref "C8") (pin "1") (pinfunction "1_1") (pintype "passive"))
      (node (ref "C9") (pin "1") (pinfunction "1_1") (pintype "passive"))
      (node (ref "J1") (pin "30") (pinfunction "30_30") (pintype "passive"))
      (node (ref "J1") (pin "31") (pinfunction "31_31") (pintype "passive"))
      (node (ref "J1") (pin "36") (pinfunction "36_36") (pintype "passive"))
      (node (ref "J1") (pin "37") (pinfunction "37_37") (pintype "passive"))
      (node (ref "J1") (pin "42") (pinfunction "42_42") (pintype "passive"))
      (node (ref "J1") (pin "45") (pinfunction "45_45") (pintype "passive"))
      (node (ref "J1") (pin "48") (pinfunction "48_48") (pintype "passive"))
      (node (ref "J1") (pin "53") (pinfunction "53_53") (pintype "passive"))
      (node (ref "J1") (pin "54") (pinfunction "54_54") (pintype "passive"))
      (node (ref "J1") (pin "59") (pinfunction "59_59") (pintype "passive"))
      (node (ref "J1") (pin "60") (pinfunction "60_60") (pintype "passive"))
      (node (ref "J1") (pin "7") (pinfunction "7_7") (pintype "passive"))
      (node (ref "J1") (pin "8") (pinfunction "8_8") (pintype "passive"))
      (node (ref "J2") (pin "15") (pinfunction "15_15") (pintype "passive"))
      (node (ref "J2") (pin "16") (pinfunction "16_16") (pintype "passive"))
      (node (ref "J2") (pin "25") (pinfunction "25_25") (pintype "passive"))
      (node (ref "J2") (pin "26") (pinfunction "26_26") (pintype "passive"))
      (node (ref "J2") (pin "35") (pinfunction "35_35") (pintype "passive"))
      (node (ref "J2") (pin "36") (pinfunction "36_36") (pintype "passive"))
      (node (ref "J2") (pin "45") (pinfunction "45_45") (pintype "passive"))
      (node (ref "J2") (pin "46") (pinfunction "46_46") (pintype "passive"))
      (node (ref "J2") (pin "5") (pinfunction "5_5") (pintype "passive"))
      (node (ref "J2") (pin "51") (pinfunction "51_51") (pintype "passive"))
      (node (ref "J2") (pin "56") (pinfunction "56_56") (pintype "passive"))
      (node (ref "J2") (pin "59") (pinfunction "59_59") (pintype "passive"))
      (node (ref "J2") (pin "6") (pinfunction "6_6") (pintype "passive"))
      (node (ref "J2") (pin "63") (pinfunction "63_63") (pintype "passive"))
      (node (ref "J2") (pin "64") (pinfunction "64_64") (pintype "passive"))
      (node (ref "J3") (pin "30") (pinfunction "30_30") (pintype "passive"))
      (node (ref "J3") (pin "31") (pinfunction "31_31") (pintype "passive"))
      (node (ref "J3") (pin "36") (pinfunction "36_36") (pintype "passive"))
      (node (ref "J3") (pin "37") (pinfunction "37_37") (pintype "passive"))
      (node (ref "J3") (pin "42") (pinfunction "42_42") (pintype "passive"))
      (node (ref "J3") (pin "45") (pinfunction "45_45") (pintype "passive"))
      (node (ref "J3") (pin "48") (pinfunction "48_48") (pintype "passive"))
      (node (ref "J3") (pin "53") (pinfunction "53_53") (pintype "passive"))
      (node (ref "J3") (pin "54") (pinfunction "54_54") (pintype "passive"))
      (node (ref "J3") (pin "59") (pinfunction "59_59") (pintype "passive"))
      (node (ref "J3") (pin "60") (pinfunction "60_60") (pintype "passive"))
      (node (ref "J3") (pin "7") (pinfunction "7_7") (pintype "passive"))
      (node (ref "J3") (pin "8") (pinfunction "8_8") (pintype "passive"))
      (node (ref "J4") (pin "15") (pinfunction "15_15") (pintype "passive"))
      (node (ref "J4") (pin "16") (pinfunction "16_16") (pintype "passive"))
      (node (ref "J4") (pin "25") (pinfunction "25_25") (pintype "passive"))
      (node (ref "J4") (pin "26") (pinfunction "26_26") (pintype "passive"))
      (node (ref "J4") (pin "35") (pinfunction "35_35") (pintype "passive"))
      (node (ref "J4") (pin "36") (pinfunction "36_36") (pintype "passive"))
      (node (ref "J4") (pin "45") (pinfunction "45_45") (pintype "passive"))
      (node (ref "J4") (pin "46") (pinfunction "46_46") (pintype "passive"))
      (node (ref "J4") (pin "5") (pinfunction "5_5") (pintype "passive"))
      (node (ref "J4") (pin "51") (pinfunction "51_51") (pintype "passive"))
      (node (ref "J4") (pin "56") (pinfunction "56_56") (pintype "passive"))
      (node (ref "J4") (pin "59") (pinfunction "59_59") (pintype "passive"))
      (node (ref "J4") (pin "6") (pinfunction "6_6") (pintype "passive"))
      (node (ref "J4") (pin "63") (pinfunction "63_63") (pintype "passive"))
      (node (ref "J4") (pin "64") (pinfunction "64_64") (pintype "passive"))
      (node (ref "J5") (pin "11") (pinfunction "11_11") (pintype "passive"))
      (node (ref "J5") (pin "12") (pinfunction "12_12") (pintype "passive"))
      (node (ref "J5") (pin "17") (pinfunction "17_17") (pintype "passive"))
      (node (ref "J5") (pin "18") (pinfunction "18_18") (pintype "passive"))
      (node (ref "J5") (pin "23") (pinfunction "23_23") (pintype "passive"))
      (node (ref "J5") (pin "24") (pinfunction "24_24") (pintype "passive"))
      (node (ref "J5") (pin "29") (pinfunction "29_29") (pintype "passive"))
      (node (ref "J5") (pin "30") (pinfunction "30_30") (pintype "passive"))
      (node (ref "J5") (pin "35") (pinfunction "35_35") (pintype "passive"))
      (node (ref "J5") (pin "36") (pinfunction "36_36") (pintype "passive"))
      (node (ref "J5") (pin "41") (pinfunction "41_41") (pintype "passive"))
      (node (ref "J5") (pin "42") (pinfunction "42_42") (pintype "passive"))
      (node (ref "J5") (pin "47") (pinfunction "47_47") (pintype "passive"))
      (node (ref "J5") (pin "48") (pinfunction "48_48") (pintype "passive"))
      (node (ref "J5") (pin "5") (pinfunction "5_5") (pintype "passive"))
      (node (ref "J5") (pin "53") (pinfunction "53_53") (pintype "passive"))
      (node (ref "J5") (pin "54") (pinfunction "54_54") (pintype "passive"))
      (node (ref "J5") (pin "59") (pinfunction "59_59") (pintype "passive"))
      (node (ref "J5") (pin "6") (pinfunction "6_6") (pintype "passive"))
      (node (ref "J5") (pin "60") (pinfunction "60_60") (pintype "passive"))
      (node (ref "J6") (pin "1") (pinfunction "1_1") (pintype "passive"))
      (node (ref "J6") (pin "11") (pinfunction "11_11") (pintype "passive"))
      (node (ref "J6") (pin "12") (pinfunction "12_12") (pintype "passive"))
      (node (ref "J6") (pin "22") (pinfunction "22_22") (pintype "passive"))
      (node (ref "J6") (pin "23") (pinfunction "23_23") (pintype "passive"))
      (node (ref "J6") (pin "29") (pinfunction "29_29") (pintype "passive"))
      (node (ref "J6") (pin "32") (pinfunction "32_32") (pintype "passive"))
      (node (ref "J6") (pin "35") (pinfunction "35_35") (pintype "passive"))
      (node (ref "J6") (pin "36") (pinfunction "36_36") (pintype "passive"))
      (node (ref "J6") (pin "41") (pinfunction "41_41") (pintype "passive"))
      (node (ref "J6") (pin "42") (pinfunction "42_42") (pintype "passive"))
      (node (ref "J6") (pin "47") (pinfunction "47_47") (pintype "passive"))
      (node (ref "J6") (pin "48") (pinfunction "48_48") (pintype "passive"))
      (node (ref "J6") (pin "53") (pinfunction "53_53") (pintype "passive"))
      (node (ref "J6") (pin "54") (pinfunction "54_54") (pintype "passive"))
      (node (ref "J6") (pin "59") (pinfunction "59_59") (pintype "passive"))
      (node (ref "J6") (pin "60") (pinfunction "60_60") (pintype "passive"))
      (node (ref "J7") (pin "11") (pinfunction "11_11") (pintype "passive"))
      (node (ref "J7") (pin "12") (pinfunction "12_12") (pintype "passive"))
      (node (ref "J7") (pin "17") (pinfunction "17_17") (pintype "passive"))
      (node (ref "J7") (pin "18") (pinfunction "18_18") (pintype "passive"))
      (node (ref "J7") (pin "23") (pinfunction "23_23") (pintype "passive"))
      (node (ref "J7") (pin "24") (pinfunction "24_24") (pintype "passive"))
      (node (ref "J7") (pin "29") (pinfunction "29_29") (pintype "passive"))
      (node (ref "J7") (pin "30") (pinfunction "30_30") (pintype "passive"))
      (node (ref "J7") (pin "35") (pinfunction "35_35") (pintype "passive"))
      (node (ref "J7") (pin "36") (pinfunction "36_36") (pintype "passive"))
      (node (ref "J7") (pin "41") (pinfunction "41_41") (pintype "passive"))
      (node (ref "J7") (pin "42") (pinfunction "42_42") (pintype "passive"))
      (node (ref "J7") (pin "47") (pinfunction "47_47") (pintype "passive"))
      (node (ref "J7") (pin "48") (pinfunction "48_48") (pintype "passive"))
      (node (ref "J7") (pin "5") (pinfunction "5_5") (pintype "passive"))
      (node (ref "J7") (pin "53") (pinfunction "53_53") (pintype "passive"))
      (node (ref "J7") (pin "54") (pinfunction "54_54") (pintype "passive"))
      (node (ref "J7") (pin "59") (pinfunction "59_59") (pintype "passive"))
      (node (ref "J7") (pin "6") (pinfunction "6_6") (pintype "passive"))
      (node (ref "J7") (pin "60") (pinfunction "60_60") (pintype "passive"))
      (node (ref "J8") (pin "1") (pinfunction "1_1") (pintype "passive"))
      (node (ref "J8") (pin "11") (pinfunction "11_11") (pintype "passive"))
      (node (ref "J8") (pin "12") (pinfunction "12_12") (pintype "passive"))
      (node (ref "J8") (pin "22") (pinfunction "22_22") (pintype "passive"))
      (node (ref "J8") (pin "23") (pinfunction "23_23") (pintype "passive"))
      (node (ref "J8") (pin "29") (pinfunction "29_29") (pintype "passive"))
      (node (ref "J8") (pin "32") (pinfunction "32_32") (pintype "passive"))
      (node (ref "J8") (pin "35") (pinfunction "35_35") (pintype "passive"))
      (node (ref "J8") (pin "36") (pinfunction "36_36") (pintype "passive"))
      (node (ref "J8") (pin "41") (pinfunction "41_41") (pintype "passive"))
      (node (ref "J8") (pin "42") (pinfunction "42_42") (pintype "passive"))
      (node (ref "J8") (pin "47") (pinfunction "47_47") (pintype "passive"))
      (node (ref "J8") (pin "48") (pinfunction "48_48") (pintype "passive"))
      (node (ref "J8") (pin "53") (pinfunction "53_53") (pintype "passive"))
      (node (ref "J8") (pin "54") (pinfunction "54_54") (pintype "passive"))
      (node (ref "J8") (pin "59") (pinfunction "59_59") (pintype "passive"))
      (node (ref "J8") (pin "60") (pinfunction "60_60") (pintype "passive"))
    )
    (net (code "154") (name "unconnected-(J1-Pad9)") (class "Default")
      (node (ref "J1") (pin "9") (pinfunction "9_9") (pintype "passive"))
    )
    (net (code "155") (name "unconnected-(J1-Pad10)") (class "Default")
      (node (ref "J1") (pin "10") (pinfunction "10_10") (pintype "passive"))
    )
    (net (code "156") (name "unconnected-(J1-Pad11)") (class "Default")
      (node (ref "J1") (pin "11") (pinfunction "11_11") (pintype "passive"))
    )
    (net (code "157") (name "unconnected-(J1-Pad12)") (class "Default")
      (node (ref "J1") (pin "12") (pinfunction "12_12") (pintype "passive"))
    )
    (net (code "158") (name "unconnected-(J1-Pad13)") (class "Default")
      (node (ref "J1") (pin "13") (pinfunction "13_13") (pintype "passive"))
    )
    (net (code "159") (name "unconnected-(J1-Pad14)") (class "Default")
      (node (ref "J1") (pin "14") (pinfunction "14_14") (pintype "passive"))
    )
    (net (code "160") (name "unconnected-(J1-Pad15)") (class "Default")
      (node (ref "J1") (pin "15") (pinfunction "15_15") (pintype "passive"))
    )
    (net (code "161") (name "unconnected-(J1-Pad16)") (class "Default")
      (node (ref "J1") (pin "16") (pinfunction "16_16") (pintype "passive"))
    )
    (net (code "162") (name "unconnected-(J1-Pad17)") (class "Default")
      (node (ref "J1") (pin "17") (pinfunction "17_17") (pintype "passive"))
    )
    (net (code "163") (name "unconnected-(J1-Pad18)") (class "Default")
      (node (ref "J1") (pin "18") (pinfunction "18_18") (pintype "passive"))
    )
    (net (code "164") (name "unconnected-(J1-Pad19)") (class "Default")
      (node (ref "J1") (pin "19") (pinfunction "19_19") (pintype "passive"))
    )
    (net (code "165") (name "unconnected-(J1-Pad20)") (class "Default")
      (node (ref "J1") (pin "20") (pinfunction "20_20") (pintype "passive"))
    )
    (net (code "166") (name "unconnected-(J1-Pad21)") (class "Default")
      (node (ref "J1") (pin "21") (pinfunction "21_21") (pintype "passive"))
    )
    (net (code "167") (name "unconnected-(J1-Pad22)") (class "Default")
      (node (ref "J1") (pin "22") (pinfunction "22_22") (pintype "passive"))
    )
    (net (code "168") (name "unconnected-(J1-Pad23)") (class "Default")
      (node (ref "J1") (pin "23") (pinfunction "23_23") (pintype "passive"))
    )
    (net (code "169") (name "unconnected-(J1-Pad24)") (class "Default")
      (node (ref "J1") (pin "24") (pinfunction "24_24") (pintype "passive"))
    )
    (net (code "170") (name "unconnected-(J1-Pad25)") (class "Default")
      (node (ref "J1") (pin "25") (pinfunction "25_25") (pintype "passive"))
    )
    (net (code "171") (name "unconnected-(J1-Pad26)") (class "Default")
      (node (ref "J1") (pin "26") (pinfunction "26_26") (pintype "passive"))
    )
    (net (code "172") (name "unconnected-(J1-Pad27)") (class "Default")
      (node (ref "J1") (pin "27") (pinfunction "27_27") (pintype "passive"))
    )
    (net (code "173") (name "unconnected-(J1-Pad28)") (class "Default")
      (node (ref "J1") (pin "28") (pinfunction "28_28") (pintype "passive"))
    )
    (net (code "174") (name "unconnected-(J1-Pad29)") (class "Default")
      (node (ref "J1") (pin "29") (pinfunction "29_29") (pintype "passive"))
    )
    (net (code "175") (name "unconnected-(J2-Pad53)") (class "Default")
      (node (ref "J2") (pin "53") (pinfunction "53_53") (pintype "passive"))
    )
    (net (code "176") (name "unconnected-(J2-Pad55)") (class "Default")
      (node (ref "J2") (pin "55") (pinfunction "55_55") (pintype "passive"))
    )
    (net (code "177") (name "unconnected-(J2-Pad57)") (class "Default")
      (node (ref "J2") (pin "57") (pinfunction "57_57") (pintype "passive"))
    )
    (net (code "178") (name "unconnected-(J3-Pad9)") (class "Default")
      (node (ref "J3") (pin "9") (pinfunction "9_9") (pintype "passive"))
    )
    (net (code "179") (name "unconnected-(J3-Pad10)") (class "Default")
      (node (ref "J3") (pin "10") (pinfunction "10_10") (pintype "passive"))
    )
    (net (code "180") (name "unconnected-(J3-Pad11)") (class "Default")
      (node (ref "J3") (pin "11") (pinfunction "11_11") (pintype "passive"))
    )
    (net (code "181") (name "unconnected-(J3-Pad12)") (class "Default")
      (node (ref "J3") (pin "12") (pinfunction "12_12") (pintype "passive"))
    )
    (net (code "182") (name "unconnected-(J3-Pad13)") (class "Default")
      (node (ref "J3") (pin "13") (pinfunction "13_13") (pintype "passive"))
    )
    (net (code "183") (name "unconnected-(J3-Pad14)") (class "Default")
      (node (ref "J3") (pin "14") (pinfunction "14_14") (pintype "passive"))
    )
    (net (code "184") (name "unconnected-(J3-Pad15)") (class "Default")
      (node (ref "J3") (pin "15") (pinfunction "15_15") (pintype "passive"))
    )
    (net (code "185") (name "unconnected-(J3-Pad16)") (class "Default")
      (node (ref "J3") (pin "16") (pinfunction "16_16") (pintype "passive"))
    )
    (net (code "186") (name "unconnected-(J3-Pad17)") (class "Default")
      (node (ref "J3") (pin "17") (pinfunction "17_17") (pintype "passive"))
    )
    (net (code "187") (name "unconnected-(J3-Pad18)") (class "Default")
      (node (ref "J3") (pin "18") (pinfunction "18_18") (pintype "passive"))
    )
    (net (code "188") (name "unconnected-(J3-Pad19)") (class "Default")
      (node (ref "J3") (pin "19") (pinfunction "19_19") (pintype "passive"))
    )
    (net (code "189") (name "unconnected-(J3-Pad20)") (class "Default")
      (node (ref "J3") (pin "20") (pinfunction "20_20") (pintype "passive"))
    )
    (net (code "190") (name "unconnected-(J3-Pad21)") (class "Default")
      (node (ref "J3") (pin "21") (pinfunction "21_21") (pintype "passive"))
    )
    (net (code "191") (name "unconnected-(J3-Pad22)") (class "Default")
      (node (ref "J3") (pin "22") (pinfunction "22_22") (pintype "passive"))
    )
    (net (code "192") (name "unconnected-(J3-Pad23)") (class "Default")
      (node (ref "J3") (pin "23") (pinfunction "23_23") (pintype "passive"))
    )
    (net (code "193") (name "unconnected-(J3-Pad24)") (class "Default")
      (node (ref "J3") (pin "24") (pinfunction "24_24") (pintype "passive"))
    )
    (net (code "194") (name "unconnected-(J3-Pad25)") (class "Default")
      (node (ref "J3") (pin "25") (pinfunction "25_25") (pintype "passive"))
    )
    (net (code "195") (name "unconnected-(J3-Pad26)") (class "Default")
      (node (ref "J3") (pin "26") (pinfunction "26_26") (pintype "passive"))
    )
    (net (code "196") (name "unconnected-(J3-Pad27)") (class "Default")
      (node (ref "J3") (pin "27") (pinfunction "27_27") (pintype "passive"))
    )
    (net (code "197") (name "unconnected-(J3-Pad28)") (class "Default")
      (node (ref "J3") (pin "28") (pinfunction "28_28") (pintype "passive"))
    )
    (net (code "198") (name "unconnected-(J3-Pad29)") (class "Default")
      (node (ref "J3") (pin "29") (pinfunction "29_29") (pintype "passive"))
    )
    (net (code "199") (name "unconnected-(J4-Pad53)") (class "Default")
      (node (ref "J4") (pin "53") (pinfunction "53_53") (pintype "passive"))
    )
    (net (code "200") (name "unconnected-(J4-Pad55)") (class "Default")
      (node (ref "J4") (pin "55") (pinfunction "55_55") (pintype "passive"))
    )
    (net (code "201") (name "unconnected-(J4-Pad57)") (class "Default")
      (node (ref "J4") (pin "57") (pinfunction "57_57") (pintype "passive"))
    )
  )
)
